# MCU.net
KiCad netlist of a schematic drawn in Altium Designer
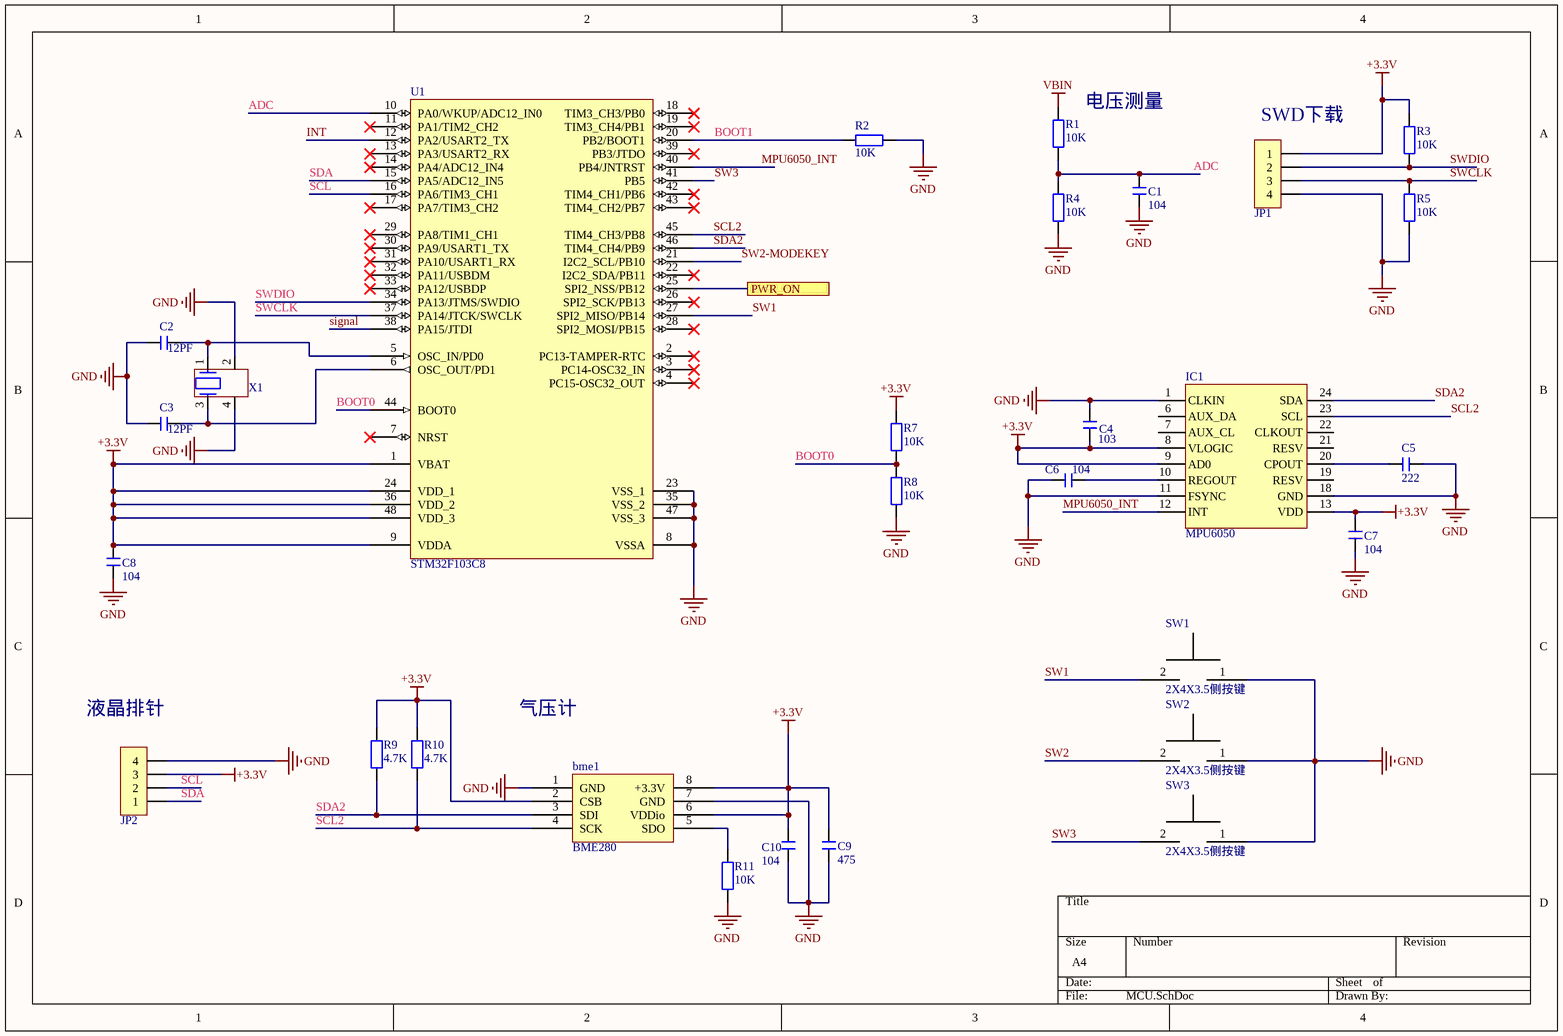
[diagram p0: MCU.SchDoc]

(export (version "E")
  (design (tool "Eeschema 10.0.6"))
  (components
    (comp (ref "bme1")
      (value "BME280")
      (footprint "BME280")
      (description "气压，湿度，温度传感器")
      (libsource (lib "我的元件") (part "BME280"))
    )
    (comp (ref "C1")
      (value "104")
      (footprint "PcbLib:C0805")
      (description "无极性贴片电容")
      (fields (field (name "版权归属") "源创客"))
      (libsource (lib "3.1   - 电阻-电容-电感") (part "C"))
    )
    (comp (ref "C2")
      (value "12PF")
      (footprint "C0603")
      (description "无极性贴片电容")
      (fields (field (name "版权归属") "源创客"))
      (libsource (lib "3.1   - 电阻-电容-电感") (part "C"))
    )
    (comp (ref "C3")
      (value "12PF")
      (footprint "C0603")
      (description "无极性贴片电容")
      (fields (field (name "版权归属") "源创客"))
      (libsource (lib "3.1   - 电阻-电容-电感") (part "C"))
    )
    (comp (ref "C4")
      (value "103")
      (footprint "C0805")
      (description "无极性贴片电容")
      (fields (field (name "版权归属") "源创客"))
      (libsource (lib "3.1   - 电阻-电容-电感") (part "C"))
    )
    (comp (ref "C5")
      (value "222")
      (footprint "C0603")
      (description "无极性贴片电容")
      (fields (field (name "版权归属") "源创客"))
      (libsource (lib "3.1   - 电阻-电容-电感") (part "C"))
    )
    (comp (ref "C6")
      (value "104")
      (footprint "C0805")
      (description "无极性贴片电容")
      (fields (field (name "版权归属") "源创客"))
      (libsource (lib "3.1   - 电阻-电容-电感") (part "C"))
    )
    (comp (ref "C7")
      (value "104")
      (footprint "C0805")
      (description "无极性贴片电容")
      (fields (field (name "版权归属") "源创客"))
      (libsource (lib "3.1   - 电阻-电容-电感") (part "C"))
    )
    (comp (ref "C8")
      (value "104")
      (footprint "C0805")
      (description "无极性贴片电容")
      (fields (field (name "版权归属") "源创客"))
      (libsource (lib "3.1   - 电阻-电容-电感") (part "C"))
    )
    (comp (ref "C9")
      (value "475")
      (footprint "C0603")
      (description "无极性贴片电容")
      (fields (field (name "版权归属") "源创客"))
      (libsource (lib "3.1   - 电阻-电容-电感") (part "C"))
    )
    (comp (ref "C10")
      (value "104")
      (footprint "C0805")
      (description "无极性贴片电容")
      (fields (field (name "版权归属") "源创客"))
      (libsource (lib "3.1   - 电阻-电容-电感") (part "C"))
    )
    (comp (ref "IC1")
      (value "MPU6050")
      (footprint "QFN24 4x4_M")
      (description "陀螺仪")
      (libsource (lib "我的元件") (part "MPU6050"))
    )
    (comp (ref "JP1")
      (value "HDR-1X4")
      (footprint "HDR1X4")
      (description "4P接插件（SWD下载）")
      (fields (field (name "MANUFACTURER") "HX(红星)"))
      (libsource (lib "MotionControl_StmH7") (part "Header 4"))
    )
    (comp (ref "JP2")
      (value "HDR-1X4")
      (footprint "HDR2.54-LI-4P")
      (description "4P接插件")
      (fields (field (name "版权归属") "源创客"))
      (libsource (lib "4.5   - 接插件-脚距2.54") (part "Header 4"))
    )
    (comp (ref "R1")
      (value "10K")
      (footprint "R0805")
      (description "贴片电阻")
      (fields (field (name "版权归属") "源创客"))
      (libsource (lib "3.1   - 电阻-电容-电感") (part "R"))
    )
    (comp (ref "R2")
      (value "10K")
      (footprint "R0805")
      (description "贴片电阻")
      (fields (field (name "版权归属") "源创客"))
      (libsource (lib "3.1   - 电阻-电容-电感") (part "R"))
    )
    (comp (ref "R3")
      (value "10K")
      (footprint "R0805")
      (description "贴片电阻")
      (fields (field (name "版权归属") "源创客"))
      (libsource (lib "3.1   - 电阻-电容-电感") (part "R"))
    )
    (comp (ref "R4")
      (value "10K")
      (footprint "R0805")
      (description "贴片电阻")
      (fields (field (name "版权归属") "源创客"))
      (libsource (lib "3.1   - 电阻-电容-电感") (part "R"))
    )
    (comp (ref "R5")
      (value "10K")
      (footprint "R0805")
      (description "贴片电阻")
      (fields (field (name "版权归属") "源创客"))
      (libsource (lib "3.1   - 电阻-电容-电感") (part "R"))
    )
    (comp (ref "R7")
      (value "10K")
      (footprint "R0805")
      (description "贴片电阻")
      (fields (field (name "版权归属") "源创客"))
      (libsource (lib "3.1   - 电阻-电容-电感") (part "R"))
    )
    (comp (ref "R8")
      (value "10K")
      (footprint "R0805")
      (description "贴片电阻")
      (fields (field (name "版权归属") "源创客"))
      (libsource (lib "3.1   - 电阻-电容-电感") (part "R"))
    )
    (comp (ref "R9")
      (value "4.7K")
      (footprint "R0805")
      (description "贴片电阻")
      (fields (field (name "版权归属") "源创客"))
      (libsource (lib "3.1   - 电阻-电容-电感") (part "R"))
    )
    (comp (ref "R10")
      (value "4.7K")
      (footprint "R0805")
      (description "贴片电阻")
      (fields (field (name "版权归属") "源创客"))
      (libsource (lib "3.1   - 电阻-电容-电感") (part "R"))
    )
    (comp (ref "R11")
      (value "10K")
      (footprint "R0805")
      (description "贴片电阻")
      (fields (field (name "版权归属") "源创客"))
      (libsource (lib "3.1   - 电阻-电容-电感") (part "R"))
    )
    (comp (ref "SW1")
      (value "2X4X3.5侧按键")
      (footprint "2X4X3.5贴片侧按开关")
      (libsource (lib "我的元件") (part "2X4X3.5侧按键"))
    )
    (comp (ref "SW2")
      (value "2X4X3.5侧按键")
      (footprint "2X4X3.5贴片侧按开关")
      (libsource (lib "我的元件") (part "2X4X3.5侧按键"))
    )
    (comp (ref "SW3")
      (value "2X4X3.5侧按键")
      (footprint "2X4X3.5贴片侧按开关")
      (libsource (lib "我的元件") (part "2X4X3.5侧按键"))
    )
    (comp (ref "U1")
      (value "STM32F103C8")
      (footprint "LQFP48 7X7_M")
      (description "Flaah:64/RAM:20/IO:36")
      (fields (field (name "版权归属") "源创客"))
      (libsource (lib "2.1   - STM32系列单片机") (part "STM32F103C8"))
    )
    (comp (ref "X1")
      (value "YSX321SL 8MHz 12pF")
      (footprint "PcbLib:3225-4N")
      (description "Crystal 8MHz, 12pF")
      (libsource (lib "MotionControl_StmH7") (part "XTAL_4_PINS"))
    )
  )
  (nets
    (net (code "1") (name "+3.3V") (class "Default")
      (node (ref "C10") (pin "2") (pinfunction "2_2") (pintype "passive"))
      (node (ref "C4") (pin "1") (pinfunction "1_1") (pintype "passive"))
      (node (ref "C7") (pin "2") (pinfunction "2_2") (pintype "passive"))
      (node (ref "C8") (pin "2") (pinfunction "2_2") (pintype "passive"))
      (node (ref "C9") (pin "2") (pinfunction "2_2") (pintype "passive"))
      (node (ref "IC1") (pin "13") (pinfunction "VDD_13") (pintype "passive"))
      (node (ref "IC1") (pin "8") (pinfunction "VLOGIC_8") (pintype "passive"))
      (node (ref "IC1") (pin "9") (pinfunction "AD0_9") (pintype "passive"))
      (node (ref "JP1") (pin "1") (pinfunction "1_1") (pintype "passive"))
      (node (ref "JP2") (pin "3") (pinfunction "3_3") (pintype "passive"))
      (node (ref "R10") (pin "2") (pinfunction "2_2") (pintype "passive"))
      (node (ref "R3") (pin "2") (pinfunction "2_2") (pintype "passive"))
      (node (ref "R7") (pin "2") (pinfunction "2_2") (pintype "passive"))
      (node (ref "R9") (pin "2") (pinfunction "2_2") (pintype "passive"))
      (node (ref "U1") (pin "1") (pinfunction "VBAT_1") (pintype "power_in"))
      (node (ref "U1") (pin "24") (pinfunction "VDD_1_24") (pintype "power_in"))
      (node (ref "U1") (pin "36") (pinfunction "VDD_2_36") (pintype "power_in"))
      (node (ref "U1") (pin "48") (pinfunction "VDD_3_48") (pintype "power_in"))
      (node (ref "U1") (pin "9") (pinfunction "VDDA_9") (pintype "power_in"))
      (node (ref "bme1") (pin "2") (pinfunction "CSB_2") (pintype "passive"))
      (node (ref "bme1") (pin "6") (pinfunction "VDDio_6") (pintype "passive"))
      (node (ref "bme1") (pin "8") (pinfunction "+3.3V_8") (pintype "passive"))
    )
    (net (code "2") (name "/ADC") (class "Default")
      (node (ref "C1") (pin "2") (pinfunction "2_2") (pintype "passive"))
      (node (ref "R1") (pin "1") (pinfunction "1_1") (pintype "passive"))
      (node (ref "R4") (pin "2") (pinfunction "2_2") (pintype "passive"))
      (node (ref "U1") (pin "10") (pinfunction "PA0/WKUP/ADC12_IN0_10") (pintype "bidirectional"))
    )
    (net (code "3") (name "/BOOT0") (class "Default")
      (node (ref "R7") (pin "1") (pinfunction "1_1") (pintype "passive"))
      (node (ref "R8") (pin "2") (pinfunction "2_2") (pintype "passive"))
      (node (ref "U1") (pin "44") (pinfunction "BOOT0_44") (pintype "input"))
    )
    (net (code "4") (name "/BOOT1") (class "Default")
      (node (ref "R2") (pin "1") (pinfunction "1_1") (pintype "passive"))
      (node (ref "U1") (pin "20") (pinfunction "PB2/BOOT1_20") (pintype "bidirectional"))
    )
    (net (code "5") (name "/INT") (class "Default")
      (node (ref "U1") (pin "12") (pinfunction "PA2/USART2_TX_12") (pintype "bidirectional"))
    )
    (net (code "6") (name "/MPU6050_INT") (class "Default")
      (node (ref "IC1") (pin "12") (pinfunction "INT_12") (pintype "passive"))
      (node (ref "U1") (pin "40") (pinfunction "PB4/JNTRST_40") (pintype "bidirectional"))
    )
    (net (code "7") (name "/PWR_ON") (class "Default")
      (node (ref "U1") (pin "25") (pinfunction "SPI2_NSS/PB12_25") (pintype "bidirectional"))
    )
    (net (code "8") (name "/SCL") (class "Default")
      (node (ref "JP2") (pin "2") (pinfunction "2_2") (pintype "passive"))
      (node (ref "U1") (pin "16") (pinfunction "PA6/TIM3_CH1_16") (pintype "bidirectional"))
    )
    (net (code "9") (name "/SCL2") (class "Default")
      (node (ref "IC1") (pin "23") (pinfunction "SCL_23") (pintype "passive"))
      (node (ref "R10") (pin "1") (pinfunction "1_1") (pintype "passive"))
      (node (ref "U1") (pin "45") (pinfunction "TIM4_CH3/PB8_45") (pintype "bidirectional"))
      (node (ref "bme1") (pin "4") (pinfunction "SCK_4") (pintype "passive"))
    )
    (net (code "10") (name "/SDA") (class "Default")
      (node (ref "JP2") (pin "1") (pinfunction "1_1") (pintype "passive"))
      (node (ref "U1") (pin "15") (pinfunction "PA5/ADC12_IN5_15") (pintype "bidirectional"))
    )
    (net (code "11") (name "/SDA2") (class "Default")
      (node (ref "IC1") (pin "24") (pinfunction "SDA_24") (pintype "passive"))
      (node (ref "R9") (pin "1") (pinfunction "1_1") (pintype "passive"))
      (node (ref "U1") (pin "46") (pinfunction "TIM4_CH4/PB9_46") (pintype "bidirectional"))
      (node (ref "bme1") (pin "3") (pinfunction "SDI_3") (pintype "passive"))
    )
    (net (code "12") (name "/SW1") (class "Default")
      (node (ref "SW1") (pin "2") (pinfunction "2_2") (pintype "passive"))
      (node (ref "U1") (pin "27") (pinfunction "SPI2_MISO/PB14_27") (pintype "bidirectional"))
    )
    (net (code "13") (name "/SW2") (class "Default")
      (node (ref "SW2") (pin "2") (pinfunction "2_2") (pintype "passive"))
    )
    (net (code "14") (name "/SW2-MODEKEY") (class "Default")
      (node (ref "U1") (pin "21") (pinfunction "I2C2_SCL/PB10_21") (pintype "bidirectional"))
    )
    (net (code "15") (name "/SW3") (class "Default")
      (node (ref "SW3") (pin "2") (pinfunction "2_2") (pintype "passive"))
      (node (ref "U1") (pin "41") (pinfunction "PB5_41") (pintype "bidirectional"))
    )
    (net (code "16") (name "/SWCLK") (class "Default")
      (node (ref "JP1") (pin "3") (pinfunction "3_3") (pintype "passive"))
      (node (ref "R5") (pin "2") (pinfunction "2_2") (pintype "passive"))
      (node (ref "U1") (pin "37") (pinfunction "PA14/JTCK/SWCLK_37") (pintype "bidirectional"))
    )
    (net (code "17") (name "/SWDIO") (class "Default")
      (node (ref "JP1") (pin "2") (pinfunction "2_2") (pintype "passive"))
      (node (ref "R3") (pin "1") (pinfunction "1_1") (pintype "passive"))
      (node (ref "U1") (pin "34") (pinfunction "PA13/JTMS/SWDIO_34") (pintype "bidirectional"))
    )
    (net (code "18") (name "/signal") (class "Default")
      (node (ref "U1") (pin "38") (pinfunction "PA15/JTDI_38") (pintype "bidirectional"))
    )
    (net (code "19") (name "GND") (class "Default")
      (node (ref "C1") (pin "1") (pinfunction "1_1") (pintype "passive"))
      (node (ref "C10") (pin "1") (pinfunction "1_1") (pintype "passive"))
      (node (ref "C2") (pin "1") (pinfunction "1_1") (pintype "passive"))
      (node (ref "C3") (pin "1") (pinfunction "1_1") (pintype "passive"))
      (node (ref "C4") (pin "2") (pinfunction "2_2") (pintype "passive"))
      (node (ref "C5") (pin "1") (pinfunction "1_1") (pintype "passive"))
      (node (ref "C6") (pin "2") (pinfunction "2_2") (pintype "passive"))
      (node (ref "C7") (pin "1") (pinfunction "1_1") (pintype "passive"))
      (node (ref "C8") (pin "1") (pinfunction "1_1") (pintype "passive"))
      (node (ref "C9") (pin "1") (pinfunction "1_1") (pintype "passive"))
      (node (ref "IC1") (pin "1") (pinfunction "CLKIN_1") (pintype "passive"))
      (node (ref "IC1") (pin "11") (pinfunction "FSYNC_11") (pintype "passive"))
      (node (ref "IC1") (pin "18") (pinfunction "GND_18") (pintype "passive"))
      (node (ref "JP1") (pin "4") (pinfunction "4_4") (pintype "passive"))
      (node (ref "JP2") (pin "4") (pinfunction "4_4") (pintype "passive"))
      (node (ref "R11") (pin "1") (pinfunction "1_1") (pintype "passive"))
      (node (ref "R2") (pin "2") (pinfunction "2_2") (pintype "passive"))
      (node (ref "R4") (pin "1") (pinfunction "1_1") (pintype "passive"))
      (node (ref "R5") (pin "1") (pinfunction "1_1") (pintype "passive"))
      (node (ref "R8") (pin "1") (pinfunction "1_1") (pintype "passive"))
      (node (ref "SW1") (pin "1") (pinfunction "1_1") (pintype "passive"))
      (node (ref "SW2") (pin "1") (pinfunction "1_1") (pintype "passive"))
      (node (ref "SW3") (pin "1") (pinfunction "1_1") (pintype "passive"))
      (node (ref "U1") (pin "23") (pinfunction "VSS_1_23") (pintype "power_in"))
      (node (ref "U1") (pin "35") (pinfunction "VSS_2_35") (pintype "power_in"))
      (node (ref "U1") (pin "47") (pinfunction "VSS_3_47") (pintype "power_in"))
      (node (ref "U1") (pin "8") (pinfunction "VSSA_8") (pintype "power_in"))
      (node (ref "X1") (pin "2") (pinfunction "2_2") (pintype "passive"))
      (node (ref "X1") (pin "4") (pinfunction "4_4") (pintype "passive"))
      (node (ref "bme1") (pin "1") (pinfunction "GND_1") (pintype "passive"))
      (node (ref "bme1") (pin "7") (pinfunction "GND_7") (pintype "passive"))
    )
    (net (code "20") (name "Net-(IC1-CPOUT)") (class "Default")
      (node (ref "C5") (pin "2") (pinfunction "2_2") (pintype "passive"))
      (node (ref "IC1") (pin "20") (pinfunction "CPOUT_20") (pintype "passive"))
    )
    (net (code "21") (name "Net-(IC1-REGOUT)") (class "Default")
      (node (ref "C6") (pin "1") (pinfunction "1_1") (pintype "passive"))
      (node (ref "IC1") (pin "10") (pinfunction "REGOUT_10") (pintype "passive"))
    )
    (net (code "22") (name "Net-(U1-OSC_IN{slash}PD0)") (class "Default")
      (node (ref "C2") (pin "2") (pinfunction "2_2") (pintype "passive"))
      (node (ref "U1") (pin "5") (pinfunction "OSC_IN/PD0_5") (pintype "input"))
      (node (ref "X1") (pin "1") (pinfunction "1_1") (pintype "passive"))
    )
    (net (code "23") (name "Net-(U1-OSC_OUT{slash}PD1)") (class "Default")
      (node (ref "C3") (pin "2") (pinfunction "2_2") (pintype "passive"))
      (node (ref "U1") (pin "6") (pinfunction "OSC_OUT/PD1_6") (pintype "output"))
      (node (ref "X1") (pin "3") (pinfunction "3_3") (pintype "passive"))
    )
    (net (code "24") (name "Net-(bme1-SDO)") (class "Default")
      (node (ref "R11") (pin "2") (pinfunction "2_2") (pintype "passive"))
      (node (ref "bme1") (pin "5") (pinfunction "SDO_5") (pintype "passive"))
    )
    (net (code "25") (name "VBIN") (class "Default")
      (node (ref "R1") (pin "2") (pinfunction "2_2") (pintype "passive"))
    )
    (net (code "26") (name "unconnected-(IC1-AUX_CL-Pad7)") (class "Default")
      (node (ref "IC1") (pin "7") (pinfunction "AUX_CL_7") (pintype "passive"))
    )
    (net (code "27") (name "unconnected-(IC1-AUX_DA-Pad6)") (class "Default")
      (node (ref "IC1") (pin "6") (pinfunction "AUX_DA_6") (pintype "passive"))
    )
    (net (code "28") (name "unconnected-(IC1-CLKOUT-Pad22)") (class "Default")
      (node (ref "IC1") (pin "22") (pinfunction "CLKOUT_22") (pintype "passive"))
    )
    (net (code "29") (name "unconnected-(IC1-RESV-Pad19)") (class "Default")
      (node (ref "IC1") (pin "19") (pinfunction "RESV_19") (pintype "passive"))
    )
    (net (code "30") (name "unconnected-(IC1-RESV-Pad21)") (class "Default")
      (node (ref "IC1") (pin "21") (pinfunction "RESV_21") (pintype "passive"))
    )
    (net (code "31") (name "unconnected-(U1-I2C2_SDA{slash}PB11-Pad22)") (class "Default")
      (node (ref "U1") (pin "22") (pinfunction "I2C2_SDA/PB11_22") (pintype "bidirectional+no_connect"))
    )
    (net (code "32") (name "unconnected-(U1-NRST-Pad7)") (class "Default")
      (node (ref "U1") (pin "7") (pinfunction "NRST_7") (pintype "bidirectional+no_connect"))
    )
    (net (code "33") (name "unconnected-(U1-PA1{slash}TIM2_CH2-Pad11)") (class "Default")
      (node (ref "U1") (pin "11") (pinfunction "PA1/TIM2_CH2_11") (pintype "bidirectional+no_connect"))
    )
    (net (code "34") (name "unconnected-(U1-PA3{slash}USART2_RX-Pad13)") (class "Default")
      (node (ref "U1") (pin "13") (pinfunction "PA3/USART2_RX_13") (pintype "bidirectional+no_connect"))
    )
    (net (code "35") (name "unconnected-(U1-PA4{slash}ADC12_IN4-Pad14)") (class "Default")
      (node (ref "U1") (pin "14") (pinfunction "PA4/ADC12_IN4_14") (pintype "bidirectional+no_connect"))
    )
    (net (code "36") (name "unconnected-(U1-PA7{slash}TIM3_CH2-Pad17)") (class "Default")
      (node (ref "U1") (pin "17") (pinfunction "PA7/TIM3_CH2_17") (pintype "bidirectional+no_connect"))
    )
    (net (code "37") (name "unconnected-(U1-PA8{slash}TIM1_CH1-Pad29)") (class "Default")
      (node (ref "U1") (pin "29") (pinfunction "PA8/TIM1_CH1_29") (pintype "bidirectional+no_connect"))
    )
    (net (code "38") (name "unconnected-(U1-PA9{slash}USART1_TX-Pad30)") (class "Default")
      (node (ref "U1") (pin "30") (pinfunction "PA9/USART1_TX_30") (pintype "bidirectional+no_connect"))
    )
    (net (code "39") (name "unconnected-(U1-PA10{slash}USART1_RX-Pad31)") (class "Default")
      (node (ref "U1") (pin "31") (pinfunction "PA10/USART1_RX_31") (pintype "bidirectional+no_connect"))
    )
    (net (code "40") (name "unconnected-(U1-PA11{slash}USBDM-Pad32)") (class "Default")
      (node (ref "U1") (pin "32") (pinfunction "PA11/USBDM_32") (pintype "bidirectional+no_connect"))
    )
    (net (code "41") (name "unconnected-(U1-PA12{slash}USBDP-Pad33)") (class "Default")
      (node (ref "U1") (pin "33") (pinfunction "PA12/USBDP_33") (pintype "bidirectional+no_connect"))
    )
    (net (code "42") (name "unconnected-(U1-PB3{slash}JTDO-Pad39)") (class "Default")
      (node (ref "U1") (pin "39") (pinfunction "PB3/JTDO_39") (pintype "bidirectional+no_connect"))
    )
    (net (code "43") (name "unconnected-(U1-PC13-TAMPER-RTC-Pad2)") (class "Default")
      (node (ref "U1") (pin "2") (pinfunction "PC13-TAMPER-RTC_2") (pintype "bidirectional+no_connect"))
    )
    (net (code "44") (name "unconnected-(U1-PC14-OSC32_IN-Pad3)") (class "Default")
      (node (ref "U1") (pin "3") (pinfunction "PC14-OSC32_IN_3") (pintype "bidirectional+no_connect"))
    )
    (net (code "45") (name "unconnected-(U1-PC15-OSC32_OUT-Pad4)") (class "Default")
      (node (ref "U1") (pin "4") (pinfunction "PC15-OSC32_OUT_4") (pintype "bidirectional+no_connect"))
    )
    (net (code "46") (name "unconnected-(U1-SPI2_MOSI{slash}PB15-Pad28)") (class "Default")
      (node (ref "U1") (pin "28") (pinfunction "SPI2_MOSI/PB15_28") (pintype "bidirectional+no_connect"))
    )
    (net (code "47") (name "unconnected-(U1-SPI2_SCK{slash}PB13-Pad26)") (class "Default")
      (node (ref "U1") (pin "26") (pinfunction "SPI2_SCK/PB13_26") (pintype "bidirectional+no_connect"))
    )
    (net (code "48") (name "unconnected-(U1-TIM3_CH3{slash}PB0-Pad18)") (class "Default")
      (node (ref "U1") (pin "18") (pinfunction "TIM3_CH3/PB0_18") (pintype "bidirectional+no_connect"))
    )
    (net (code "49") (name "unconnected-(U1-TIM3_CH4{slash}PB1-Pad19)") (class "Default")
      (node (ref "U1") (pin "19") (pinfunction "TIM3_CH4/PB1_19") (pintype "bidirectional+no_connect"))
    )
    (net (code "50") (name "unconnected-(U1-TIM4_CH1{slash}PB6-Pad42)") (class "Default")
      (node (ref "U1") (pin "42") (pinfunction "TIM4_CH1/PB6_42") (pintype "bidirectional+no_connect"))
    )
    (net (code "51") (name "unconnected-(U1-TIM4_CH2{slash}PB7-Pad43)") (class "Default")
      (node (ref "U1") (pin "43") (pinfunction "TIM4_CH2/PB7_43") (pintype "bidirectional+no_connect"))
    )
  )
)
